# device.net
KiCad netlist of a schematic drawn in EAGLE
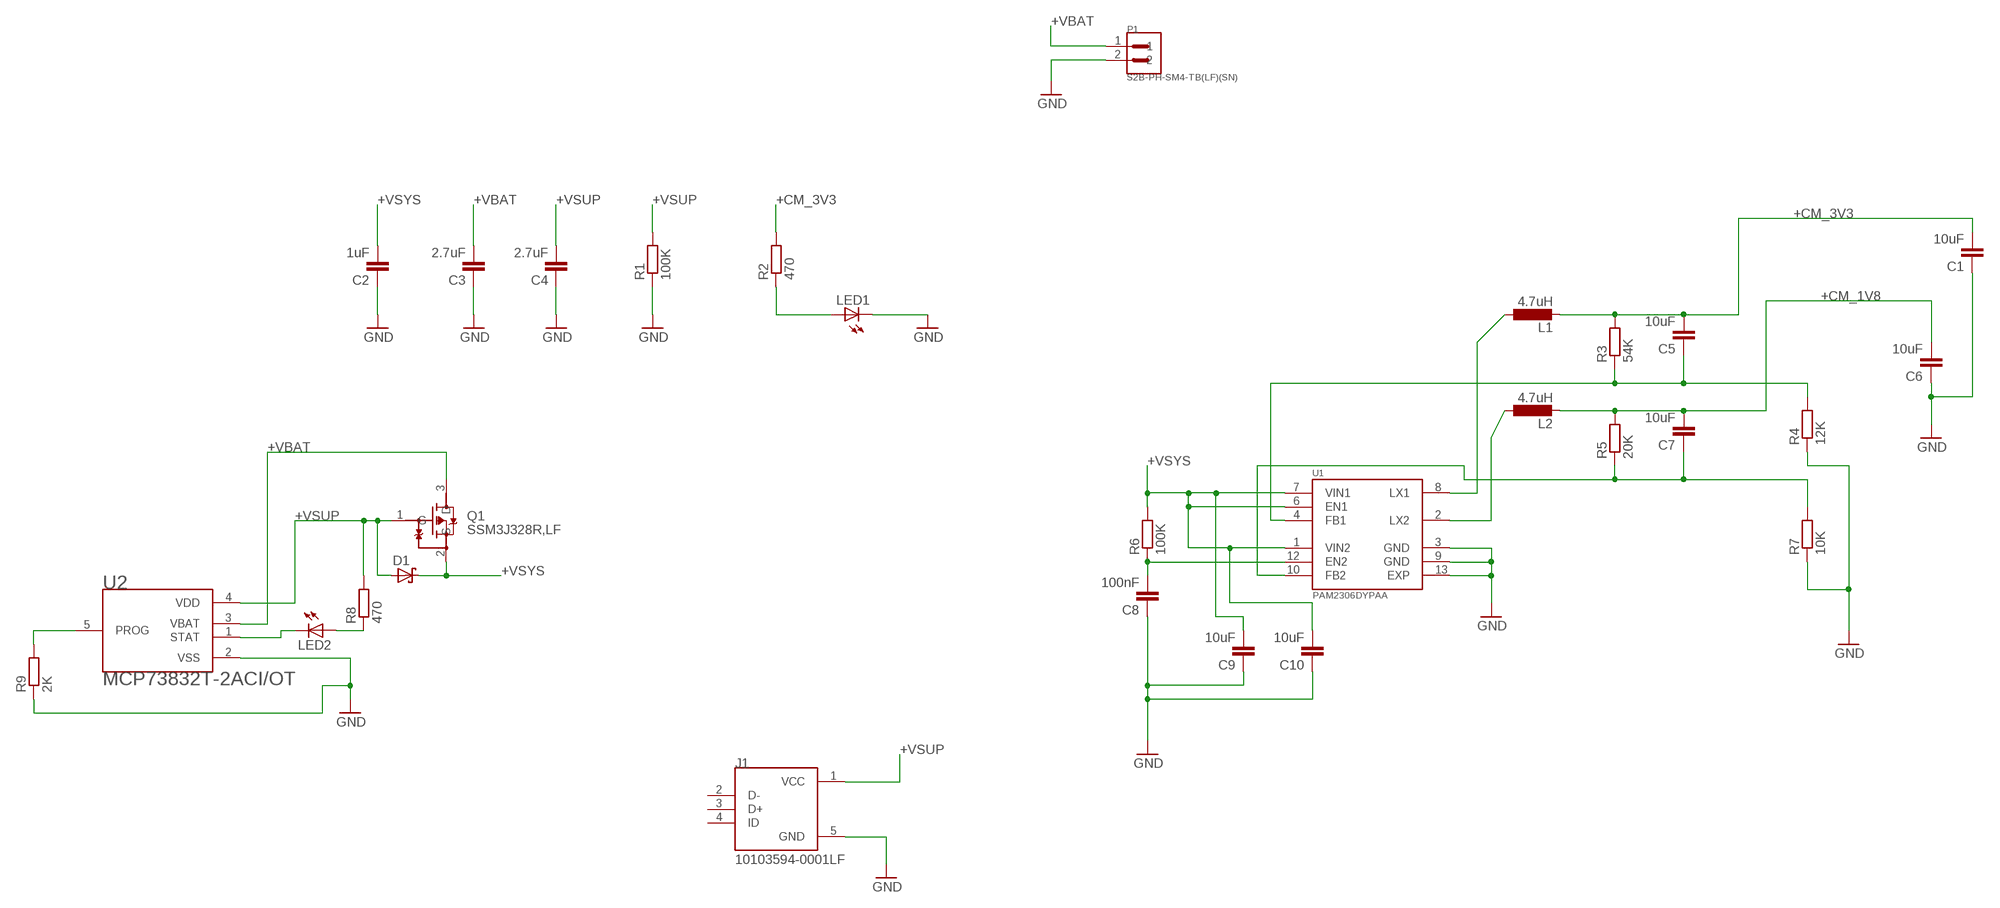
[diagram p0: schematic, sheet 1, part 1 of 2]
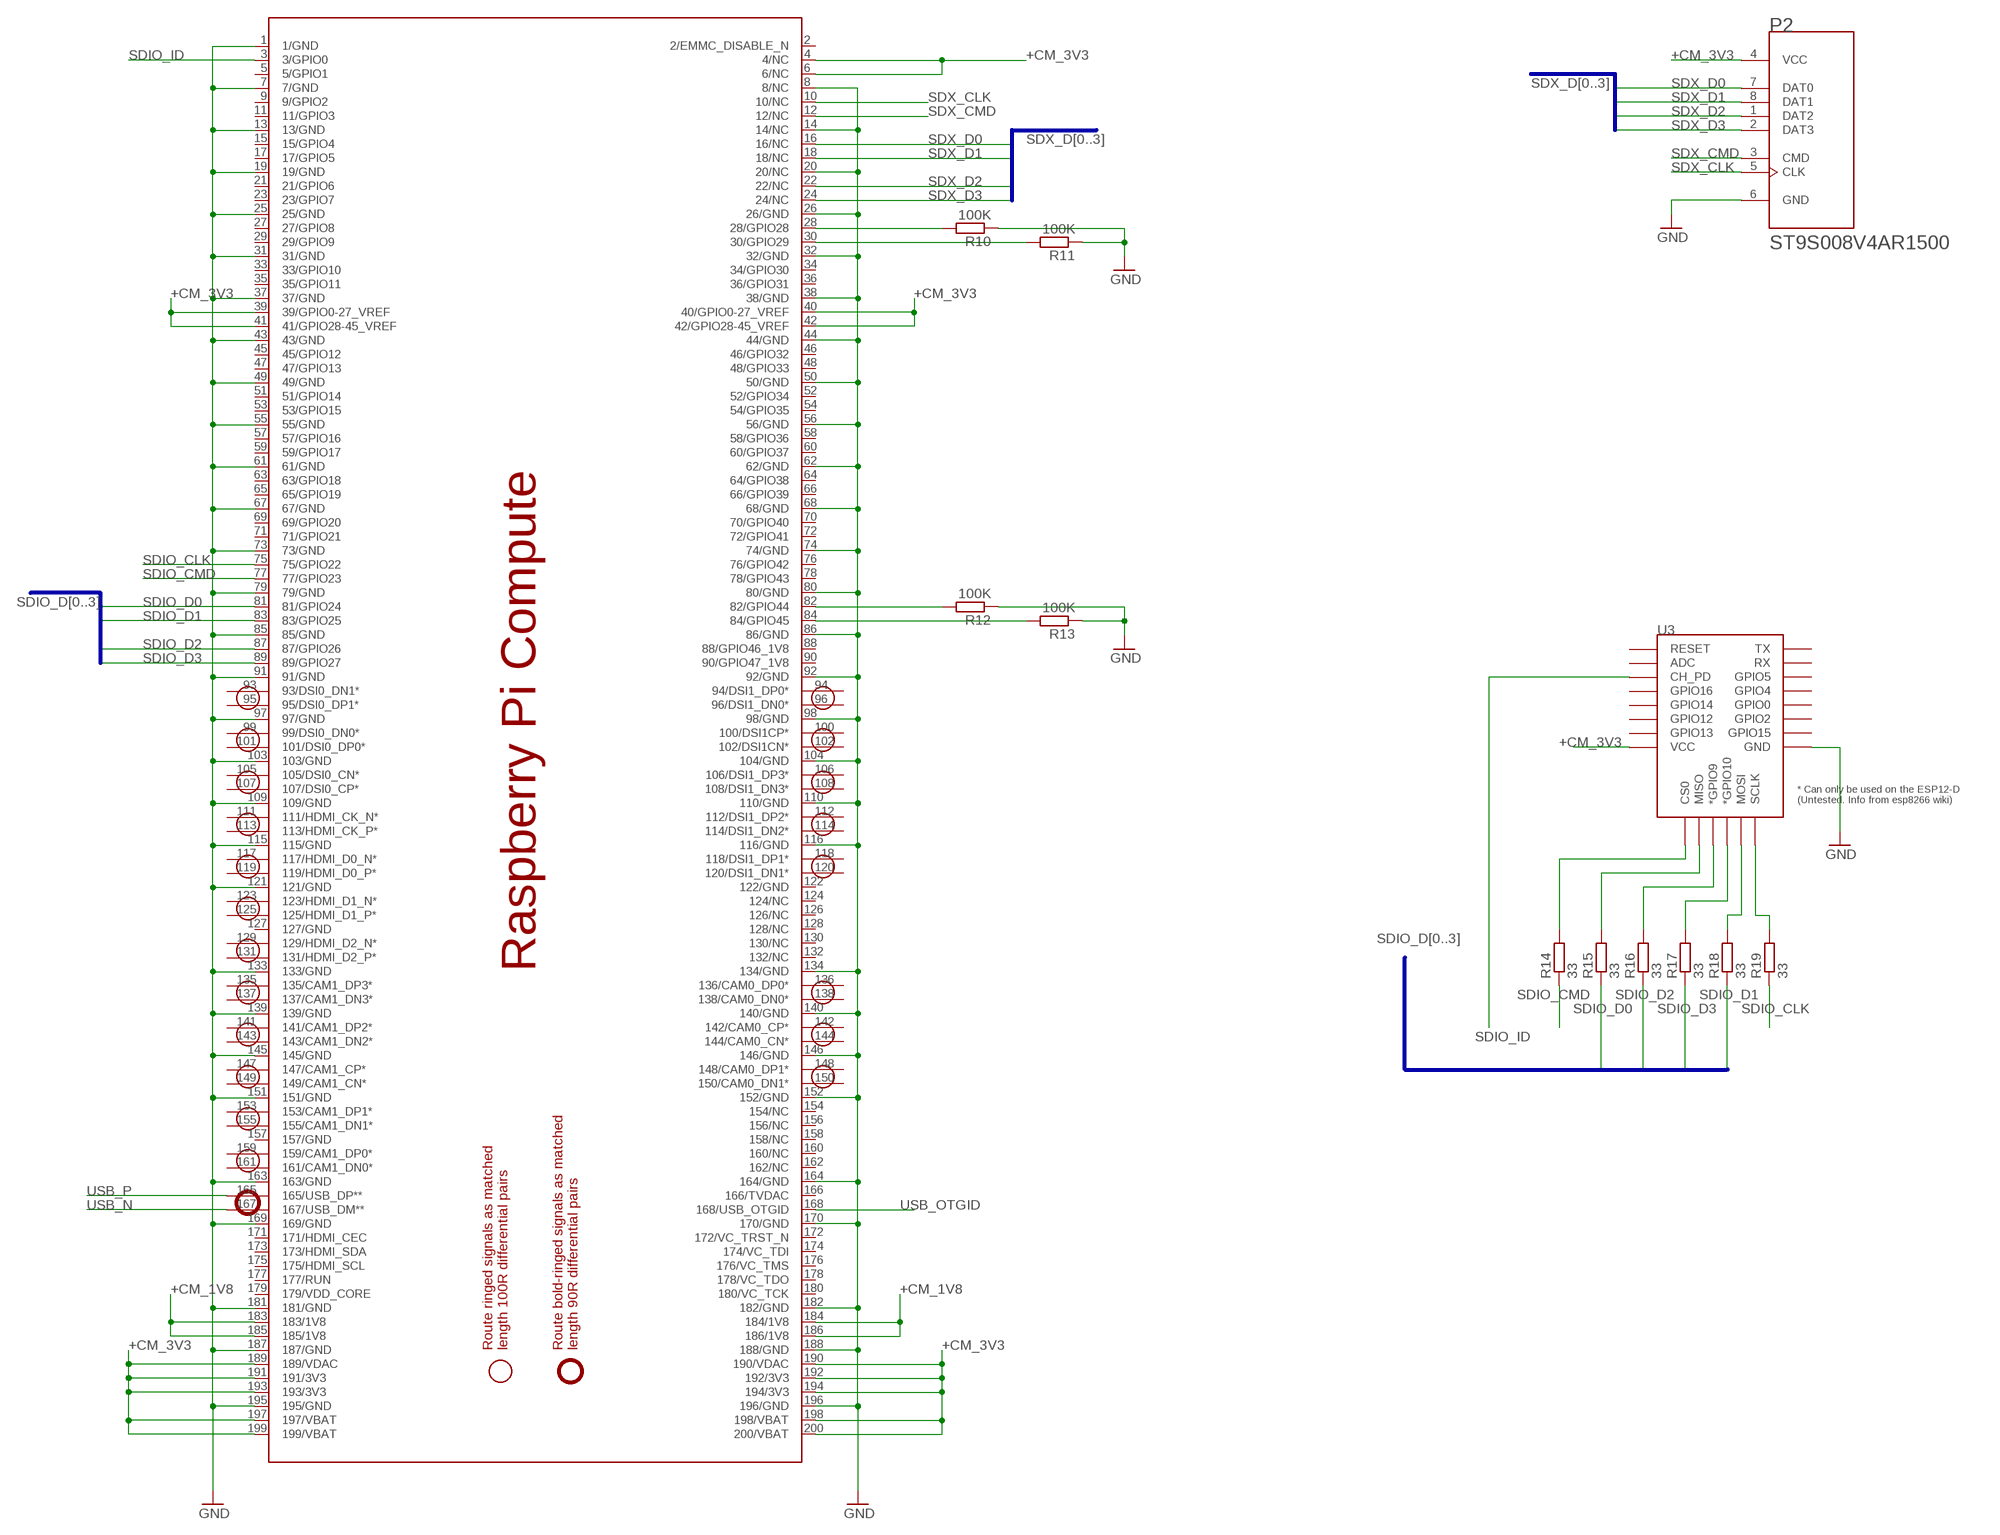
[diagram p1: schematic, sheet 1, part 2 of 2]

(export (version "E")
  (design (tool "Eeschema 10.0.6"))
  (components
    (comp (ref "C1")
      (value "10uF")
      (footprint "eagle-import:C0603")
      (libsource (lib "eagle-import") (part "C-EUC0603"))
    )
    (comp (ref "C2")
      (value "1uF")
      (footprint "eagle-import:C0603")
      (libsource (lib "eagle-import") (part "C-EUC0603"))
    )
    (comp (ref "C3")
      (value "2.7uF")
      (footprint "eagle-import:C0603")
      (libsource (lib "eagle-import") (part "C-EUC0603"))
    )
    (comp (ref "C4")
      (value "2.7uF")
      (footprint "eagle-import:C0603")
      (libsource (lib "eagle-import") (part "C-EUC0603"))
    )
    (comp (ref "C5")
      (value "10uF")
      (footprint "eagle-import:C0603")
      (libsource (lib "eagle-import") (part "C-EUC0603"))
    )
    (comp (ref "C6")
      (value "10uF")
      (footprint "eagle-import:C0603")
      (libsource (lib "eagle-import") (part "C-EUC0603"))
    )
    (comp (ref "C7")
      (value "10uF")
      (footprint "eagle-import:C0603")
      (libsource (lib "eagle-import") (part "C-EUC0603"))
    )
    (comp (ref "C8")
      (value "100nF")
      (footprint "eagle-import:C0603")
      (libsource (lib "eagle-import") (part "C-EUC0603"))
    )
    (comp (ref "C9")
      (value "10uF")
      (footprint "eagle-import:C0603")
      (libsource (lib "eagle-import") (part "C-EUC0603"))
    )
    (comp (ref "C10")
      (value "10uF")
      (footprint "eagle-import:C0603")
      (libsource (lib "eagle-import") (part "C-EUC0603"))
    )
    (comp (ref "D1")
      (value "SCHOTTKY-DIODESMD")
      (footprint "eagle-import:SMB")
      (libsource (lib "eagle-import") (part "SCHOTTKY-DIODESMD"))
    )
    (comp (ref "J1")
      (value "10103594-0001LF")
      (footprint "eagle-import:FCI_10103594-0001LF")
      (fields (field (name "MANUFACTURER") "Framatome"))
      (libsource (lib "eagle-import") (part "10103594-0001LF"))
    )
    (comp (ref "L1")
      (value "4.7uH")
      (footprint "eagle-import:L1812")
      (libsource (lib "eagle-import") (part "L-EUL1812"))
    )
    (comp (ref "L2")
      (value "4.7uH")
      (footprint "eagle-import:L1812")
      (libsource (lib "eagle-import") (part "L-EUL1812"))
    )
    (comp (ref "LED1")
      (value "LEDCHIP-LED0603")
      (footprint "eagle-import:CHIP-LED0603")
      (libsource (lib "eagle-import") (part "LEDCHIP-LED0603"))
    )
    (comp (ref "LED2")
      (value "LEDCHIP-LED0603")
      (footprint "eagle-import:CHIP-LED0603")
      (libsource (lib "eagle-import") (part "LEDCHIP-LED0603"))
    )
    (comp (ref "P1")
      (value "S2B-PH-SM4-TB(LF)(SN)")
      (footprint "eagle-import:JST_S2B-PH-SM4-TB(LF)(SN)")
      (fields (field (name "MANUFACTURER") "JST"))
      (libsource (lib "eagle-import") (part "S2B-PH-SM4-TB(LF)(SN)"))
    )
    (comp (ref "P2")
      (value "ST9S008V4AR1500")
      (footprint "eagle-import:JAE_ST9S008V4AR1500")
      (fields (field (name "MANUFACTURER") "JAE"))
      (libsource (lib "eagle-import") (part "ST9S008V4AR1500"))
    )
    (comp (ref "PCB1")
      (value "RPI_COMPUTE")
      (footprint "eagle-import:RPI_COMPUTE")
      (libsource (lib "eagle-import") (part "RPI_COMPUTE"))
    )
    (comp (ref "Q1")
      (value "SSM3J328R,LF")
      (footprint "eagle-import:SOT95P240X88-3N")
      (fields (field (name "MANUFACTURER") "Toshiba"))
      (libsource (lib "eagle-import") (part "SSM3J328R,LF"))
    )
    (comp (ref "R1")
      (value "100K")
      (footprint "eagle-import:R0603")
      (libsource (lib "eagle-import") (part "R-EU_R0603"))
    )
    (comp (ref "R2")
      (value "470")
      (footprint "eagle-import:R0603")
      (libsource (lib "eagle-import") (part "R-EU_R0603"))
    )
    (comp (ref "R3")
      (value "54K")
      (footprint "eagle-import:R0603")
      (libsource (lib "eagle-import") (part "R-EU_R0603"))
    )
    (comp (ref "R4")
      (value "12K")
      (footprint "eagle-import:R0603")
      (libsource (lib "eagle-import") (part "R-EU_R0603"))
    )
    (comp (ref "R5")
      (value "20K")
      (footprint "eagle-import:R0603")
      (libsource (lib "eagle-import") (part "R-EU_R0603"))
    )
    (comp (ref "R6")
      (value "100K")
      (footprint "eagle-import:R0603")
      (libsource (lib "eagle-import") (part "R-EU_R0603"))
    )
    (comp (ref "R7")
      (value "10K")
      (footprint "eagle-import:R0603")
      (libsource (lib "eagle-import") (part "R-EU_R0603"))
    )
    (comp (ref "R8")
      (value "470")
      (footprint "eagle-import:R0603")
      (libsource (lib "eagle-import") (part "R-EU_R0603"))
    )
    (comp (ref "R9")
      (value "2K")
      (footprint "eagle-import:R0603")
      (libsource (lib "eagle-import") (part "R-EU_R0603"))
    )
    (comp (ref "R10")
      (value "100K")
      (footprint "eagle-import:R0603")
      (libsource (lib "eagle-import") (part "R-EU_R0603"))
    )
    (comp (ref "R11")
      (value "100K")
      (footprint "eagle-import:R0603")
      (libsource (lib "eagle-import") (part "R-EU_R0603"))
    )
    (comp (ref "R12")
      (value "100K")
      (footprint "eagle-import:R0603")
      (libsource (lib "eagle-import") (part "R-EU_R0603"))
    )
    (comp (ref "R13")
      (value "100K")
      (footprint "eagle-import:R0603")
      (libsource (lib "eagle-import") (part "R-EU_R0603"))
    )
    (comp (ref "R14")
      (value "33")
      (footprint "eagle-import:R0603")
      (libsource (lib "eagle-import") (part "R-EU_R0603"))
    )
    (comp (ref "R15")
      (value "33")
      (footprint "eagle-import:R0603")
      (libsource (lib "eagle-import") (part "R-EU_R0603"))
    )
    (comp (ref "R16")
      (value "33")
      (footprint "eagle-import:R0603")
      (libsource (lib "eagle-import") (part "R-EU_R0603"))
    )
    (comp (ref "R17")
      (value "33")
      (footprint "eagle-import:R0603")
      (libsource (lib "eagle-import") (part "R-EU_R0603"))
    )
    (comp (ref "R18")
      (value "33")
      (footprint "eagle-import:R0603")
      (libsource (lib "eagle-import") (part "R-EU_R0603"))
    )
    (comp (ref "R19")
      (value "33")
      (footprint "eagle-import:R0603")
      (libsource (lib "eagle-import") (part "R-EU_R0603"))
    )
    (comp (ref "U1")
      (value "PAM2306DYPAA")
      (footprint "eagle-import:SON45P300X300X80-13N")
      (fields (field (name "MF") "Diodes Inc."))
      (libsource (lib "eagle-import") (part "PAM2306DYPAA"))
    )
    (comp (ref "U2")
      (value "MCP73832T-2ACI/OT")
      (footprint "eagle-import:SOT95P270X145-5N")
      (fields (field (name "MANUFACTURER") "Microchip"))
      (libsource (lib "eagle-import") (part "MCP73832T-2ACI/OT"))
    )
    (comp (ref "U3")
      (value "ESP12ESMD")
      (footprint "eagle-import:ESP12E-SMD")
      (libsource (lib "eagle-import") (part "ESP12ESMD"))
    )
  )
  (nets
    (net (code "1") (name "/+CM_1V8") (class "Default")
      (node (ref "C6") (pin "2") (pinfunction "2_2") (pintype "passive"))
      (node (ref "C7") (pin "2") (pinfunction "2_2") (pintype "passive"))
      (node (ref "L2") (pin "2") (pinfunction "2_2") (pintype "passive"))
      (node (ref "PCB1") (pin "183") (pinfunction "183/1V8_183") (pintype "bidirectional"))
      (node (ref "PCB1") (pin "184") (pinfunction "184/1V8_184") (pintype "bidirectional"))
      (node (ref "PCB1") (pin "185") (pinfunction "185/1V8_185") (pintype "bidirectional"))
      (node (ref "PCB1") (pin "186") (pinfunction "186/1V8_186") (pintype "bidirectional"))
      (node (ref "R5") (pin "2") (pinfunction "2_2") (pintype "passive"))
    )
    (net (code "2") (name "/+CM_3V3") (class "Default")
      (node (ref "C1") (pin "2") (pinfunction "2_2") (pintype "passive"))
      (node (ref "C5") (pin "2") (pinfunction "2_2") (pintype "passive"))
      (node (ref "L1") (pin "2") (pinfunction "2_2") (pintype "passive"))
      (node (ref "P2") (pin "4") (pinfunction "VCC_4") (pintype "power_in"))
      (node (ref "PCB1") (pin "189") (pinfunction "189/VDAC_189") (pintype "bidirectional"))
      (node (ref "PCB1") (pin "190") (pinfunction "190/VDAC_190") (pintype "bidirectional"))
      (node (ref "PCB1") (pin "191") (pinfunction "191/3V3_191") (pintype "bidirectional"))
      (node (ref "PCB1") (pin "192") (pinfunction "192/3V3_192") (pintype "bidirectional"))
      (node (ref "PCB1") (pin "193") (pinfunction "193/3V3_193") (pintype "bidirectional"))
      (node (ref "PCB1") (pin "194") (pinfunction "194/3V3_194") (pintype "bidirectional"))
      (node (ref "PCB1") (pin "197") (pinfunction "197/VBAT_197") (pintype "bidirectional"))
      (node (ref "PCB1") (pin "198") (pinfunction "198/VBAT_198") (pintype "bidirectional"))
      (node (ref "PCB1") (pin "199") (pinfunction "199/VBAT_199") (pintype "bidirectional"))
      (node (ref "PCB1") (pin "200") (pinfunction "200/VBAT_200") (pintype "bidirectional"))
      (node (ref "PCB1") (pin "39") (pinfunction "39/GPIO0-27_VREF_39") (pintype "bidirectional"))
      (node (ref "PCB1") (pin "4") (pinfunction "4/NC_4") (pintype "bidirectional"))
      (node (ref "PCB1") (pin "40") (pinfunction "40/GPIO0-27_VREF_40") (pintype "bidirectional"))
      (node (ref "PCB1") (pin "41") (pinfunction "41/GPIO28-45_VREF_41") (pintype "bidirectional"))
      (node (ref "PCB1") (pin "42") (pinfunction "42/GPIO28-45_VREF_42") (pintype "bidirectional"))
      (node (ref "PCB1") (pin "6") (pinfunction "6/NC_6") (pintype "bidirectional"))
      (node (ref "R2") (pin "2") (pinfunction "2_2") (pintype "passive"))
      (node (ref "R3") (pin "2") (pinfunction "2_2") (pintype "passive"))
      (node (ref "U3") (pin "VCC") (pinfunction "VCC_VCC") (pintype "bidirectional"))
    )
    (net (code "3") (name "/+VBAT") (class "Default")
      (node (ref "C3") (pin "2") (pinfunction "2_2") (pintype "passive"))
      (node (ref "P1") (pin "1") (pinfunction "1_1") (pintype "passive"))
      (node (ref "Q1") (pin "3") (pinfunction "D_3") (pintype "passive"))
      (node (ref "U2") (pin "3") (pinfunction "VBAT_3") (pintype "output"))
    )
    (net (code "4") (name "/+VSUP") (class "Default")
      (node (ref "C4") (pin "2") (pinfunction "2_2") (pintype "passive"))
      (node (ref "D1") (pin "A") (pinfunction "A_A") (pintype "passive"))
      (node (ref "J1") (pin "1") (pinfunction "VCC_1") (pintype "power_in"))
      (node (ref "Q1") (pin "1") (pinfunction "G_1") (pintype "passive"))
      (node (ref "R1") (pin "2") (pinfunction "2_2") (pintype "passive"))
      (node (ref "R8") (pin "2") (pinfunction "2_2") (pintype "passive"))
      (node (ref "U2") (pin "4") (pinfunction "VDD_4") (pintype "power_in"))
    )
    (net (code "5") (name "/+VSYS") (class "Default")
      (node (ref "C10") (pin "2") (pinfunction "2_2") (pintype "passive"))
      (node (ref "C2") (pin "2") (pinfunction "2_2") (pintype "passive"))
      (node (ref "C9") (pin "2") (pinfunction "2_2") (pintype "passive"))
      (node (ref "D1") (pin "C") (pinfunction "C_C") (pintype "passive"))
      (node (ref "Q1") (pin "2") (pinfunction "S_2") (pintype "passive"))
      (node (ref "R6") (pin "2") (pinfunction "2_2") (pintype "passive"))
      (node (ref "U1") (pin "1") (pinfunction "VIN2_1") (pintype "input"))
      (node (ref "U1") (pin "6") (pinfunction "EN1_6") (pintype "input"))
      (node (ref "U1") (pin "7") (pinfunction "VIN1_7") (pintype "input"))
    )
    (net (code "6") (name "/SDIO_CLK") (class "Default")
      (node (ref "PCB1") (pin "75") (pinfunction "75/GPIO22_75") (pintype "bidirectional"))
      (node (ref "R19") (pin "1") (pinfunction "1_1") (pintype "passive"))
    )
    (net (code "7") (name "/SDIO_CMD") (class "Default")
      (node (ref "PCB1") (pin "77") (pinfunction "77/GPIO23_77") (pintype "bidirectional"))
      (node (ref "R14") (pin "1") (pinfunction "1_1") (pintype "passive"))
    )
    (net (code "8") (name "/SDIO_D0") (class "Default")
      (node (ref "PCB1") (pin "81") (pinfunction "81/GPIO24_81") (pintype "bidirectional"))
      (node (ref "R15") (pin "1") (pinfunction "1_1") (pintype "passive"))
    )
    (net (code "9") (name "/SDIO_D1") (class "Default")
      (node (ref "PCB1") (pin "83") (pinfunction "83/GPIO25_83") (pintype "bidirectional"))
      (node (ref "R18") (pin "1") (pinfunction "1_1") (pintype "passive"))
    )
    (net (code "10") (name "/SDIO_D2") (class "Default")
      (node (ref "PCB1") (pin "87") (pinfunction "87/GPIO26_87") (pintype "bidirectional"))
      (node (ref "R16") (pin "1") (pinfunction "1_1") (pintype "passive"))
    )
    (net (code "11") (name "/SDIO_D3") (class "Default")
      (node (ref "PCB1") (pin "89") (pinfunction "89/GPIO27_89") (pintype "bidirectional"))
      (node (ref "R17") (pin "1") (pinfunction "1_1") (pintype "passive"))
    )
    (net (code "13") (name "/SDIO_ID") (class "Default")
      (node (ref "PCB1") (pin "3") (pinfunction "3/GPIO0_3") (pintype "bidirectional"))
      (node (ref "U3") (pin "CH_PD") (pinfunction "CH_PD_CH_PD") (pintype "bidirectional"))
    )
    (net (code "14") (name "/SDX_CLK") (class "Default")
      (node (ref "P2") (pin "5") (pinfunction "CLK_5") (pintype "input"))
      (node (ref "PCB1") (pin "10") (pinfunction "10/NC_10") (pintype "bidirectional"))
    )
    (net (code "15") (name "/SDX_CMD") (class "Default")
      (node (ref "P2") (pin "3") (pinfunction "CMD_3") (pintype "input"))
      (node (ref "PCB1") (pin "12") (pinfunction "12/NC_12") (pintype "bidirectional"))
    )
    (net (code "16") (name "/SDX_D0") (class "Default")
      (node (ref "P2") (pin "7") (pinfunction "DAT0_7") (pintype "bidirectional"))
      (node (ref "PCB1") (pin "16") (pinfunction "16/NC_16") (pintype "bidirectional"))
    )
    (net (code "17") (name "/SDX_D1") (class "Default")
      (node (ref "P2") (pin "8") (pinfunction "DAT1_8") (pintype "bidirectional"))
      (node (ref "PCB1") (pin "18") (pinfunction "18/NC_18") (pintype "bidirectional"))
    )
    (net (code "18") (name "/SDX_D2") (class "Default")
      (node (ref "P2") (pin "1") (pinfunction "DAT2_1") (pintype "bidirectional"))
      (node (ref "PCB1") (pin "22") (pinfunction "22/NC_22") (pintype "bidirectional"))
    )
    (net (code "19") (name "/SDX_D3") (class "Default")
      (node (ref "P2") (pin "2") (pinfunction "DAT3_2") (pintype "bidirectional"))
      (node (ref "PCB1") (pin "24") (pinfunction "24/NC_24") (pintype "bidirectional"))
    )
    (net (code "21") (name "/USB_N") (class "Default")
      (node (ref "PCB1") (pin "167") (pinfunction "167/USB_DM**_167") (pintype "bidirectional"))
    )
    (net (code "22") (name "/USB_OTGID") (class "Default")
      (node (ref "PCB1") (pin "168") (pinfunction "168/USB_OTGID_168") (pintype "bidirectional"))
    )
    (net (code "23") (name "/USB_P") (class "Default")
      (node (ref "PCB1") (pin "165") (pinfunction "165/USB_DP**_165") (pintype "bidirectional"))
    )
    (net (code "24") (name "GND") (class "Default")
      (node (ref "C1") (pin "1") (pinfunction "1_1") (pintype "passive"))
      (node (ref "C10") (pin "1") (pinfunction "1_1") (pintype "passive"))
      (node (ref "C2") (pin "1") (pinfunction "1_1") (pintype "passive"))
      (node (ref "C3") (pin "1") (pinfunction "1_1") (pintype "passive"))
      (node (ref "C4") (pin "1") (pinfunction "1_1") (pintype "passive"))
      (node (ref "C6") (pin "1") (pinfunction "1_1") (pintype "passive"))
      (node (ref "C8") (pin "1") (pinfunction "1_1") (pintype "passive"))
      (node (ref "C9") (pin "1") (pinfunction "1_1") (pintype "passive"))
      (node (ref "J1") (pin "5") (pinfunction "GND_5") (pintype "power_in"))
      (node (ref "LED1") (pin "C") (pinfunction "C_C") (pintype "passive"))
      (node (ref "P1") (pin "2") (pinfunction "2_2") (pintype "passive"))
      (node (ref "P2") (pin "6") (pinfunction "GND_6") (pintype "power_in"))
      (node (ref "PCB1") (pin "1") (pinfunction "1/GND_1") (pintype "bidirectional"))
      (node (ref "PCB1") (pin "103") (pinfunction "103/GND_103") (pintype "bidirectional"))
      (node (ref "PCB1") (pin "104") (pinfunction "104/GND_104") (pintype "bidirectional"))
      (node (ref "PCB1") (pin "109") (pinfunction "109/GND_109") (pintype "bidirectional"))
      (node (ref "PCB1") (pin "110") (pinfunction "110/GND_110") (pintype "bidirectional"))
      (node (ref "PCB1") (pin "115") (pinfunction "115/GND_115") (pintype "bidirectional"))
      (node (ref "PCB1") (pin "116") (pinfunction "116/GND_116") (pintype "bidirectional"))
      (node (ref "PCB1") (pin "121") (pinfunction "121/GND_121") (pintype "bidirectional"))
      (node (ref "PCB1") (pin "13") (pinfunction "13/GND_13") (pintype "bidirectional"))
      (node (ref "PCB1") (pin "133") (pinfunction "133/GND_133") (pintype "bidirectional"))
      (node (ref "PCB1") (pin "134") (pinfunction "134/GND_134") (pintype "bidirectional"))
      (node (ref "PCB1") (pin "139") (pinfunction "139/GND_139") (pintype "bidirectional"))
      (node (ref "PCB1") (pin "14") (pinfunction "14/NC_14") (pintype "bidirectional"))
      (node (ref "PCB1") (pin "140") (pinfunction "140/GND_140") (pintype "bidirectional"))
      (node (ref "PCB1") (pin "145") (pinfunction "145/GND_145") (pintype "bidirectional"))
      (node (ref "PCB1") (pin "146") (pinfunction "146/GND_146") (pintype "bidirectional"))
      (node (ref "PCB1") (pin "151") (pinfunction "151/GND_151") (pintype "bidirectional"))
      (node (ref "PCB1") (pin "152") (pinfunction "152/GND_152") (pintype "bidirectional"))
      (node (ref "PCB1") (pin "163") (pinfunction "163/GND_163") (pintype "bidirectional"))
      (node (ref "PCB1") (pin "164") (pinfunction "164/GND_164") (pintype "bidirectional"))
      (node (ref "PCB1") (pin "169") (pinfunction "169/GND_169") (pintype "bidirectional"))
      (node (ref "PCB1") (pin "170") (pinfunction "170/GND_170") (pintype "bidirectional"))
      (node (ref "PCB1") (pin "181") (pinfunction "181/GND_181") (pintype "bidirectional"))
      (node (ref "PCB1") (pin "182") (pinfunction "182/GND_182") (pintype "bidirectional"))
      (node (ref "PCB1") (pin "187") (pinfunction "187/GND_187") (pintype "bidirectional"))
      (node (ref "PCB1") (pin "188") (pinfunction "188/GND_188") (pintype "bidirectional"))
      (node (ref "PCB1") (pin "19") (pinfunction "19/GND_19") (pintype "bidirectional"))
      (node (ref "PCB1") (pin "195") (pinfunction "195/GND_195") (pintype "bidirectional"))
      (node (ref "PCB1") (pin "196") (pinfunction "196/GND_196") (pintype "bidirectional"))
      (node (ref "PCB1") (pin "20") (pinfunction "20/NC_20") (pintype "bidirectional"))
      (node (ref "PCB1") (pin "25") (pinfunction "25/GND_25") (pintype "bidirectional"))
      (node (ref "PCB1") (pin "26") (pinfunction "26/GND_26") (pintype "bidirectional"))
      (node (ref "PCB1") (pin "31") (pinfunction "31/GND_31") (pintype "bidirectional"))
      (node (ref "PCB1") (pin "32") (pinfunction "32/GND_32") (pintype "bidirectional"))
      (node (ref "PCB1") (pin "37") (pinfunction "37/GND_37") (pintype "bidirectional"))
      (node (ref "PCB1") (pin "38") (pinfunction "38/GND_38") (pintype "bidirectional"))
      (node (ref "PCB1") (pin "43") (pinfunction "43/GND_43") (pintype "bidirectional"))
      (node (ref "PCB1") (pin "44") (pinfunction "44/GND_44") (pintype "bidirectional"))
      (node (ref "PCB1") (pin "49") (pinfunction "49/GND_49") (pintype "bidirectional"))
      (node (ref "PCB1") (pin "50") (pinfunction "50/GND_50") (pintype "bidirectional"))
      (node (ref "PCB1") (pin "55") (pinfunction "55/GND_55") (pintype "bidirectional"))
      (node (ref "PCB1") (pin "56") (pinfunction "56/GND_56") (pintype "bidirectional"))
      (node (ref "PCB1") (pin "61") (pinfunction "61/GND_61") (pintype "bidirectional"))
      (node (ref "PCB1") (pin "62") (pinfunction "62/GND_62") (pintype "bidirectional"))
      (node (ref "PCB1") (pin "67") (pinfunction "67/GND_67") (pintype "bidirectional"))
      (node (ref "PCB1") (pin "68") (pinfunction "68/GND_68") (pintype "bidirectional"))
      (node (ref "PCB1") (pin "7") (pinfunction "7/GND_7") (pintype "bidirectional"))
      (node (ref "PCB1") (pin "73") (pinfunction "73/GND_73") (pintype "bidirectional"))
      (node (ref "PCB1") (pin "74") (pinfunction "74/GND_74") (pintype "bidirectional"))
      (node (ref "PCB1") (pin "79") (pinfunction "79/GND_79") (pintype "bidirectional"))
      (node (ref "PCB1") (pin "8") (pinfunction "8/NC_8") (pintype "bidirectional"))
      (node (ref "PCB1") (pin "80") (pinfunction "80/GND_80") (pintype "bidirectional"))
      (node (ref "PCB1") (pin "85") (pinfunction "85/GND_85") (pintype "bidirectional"))
      (node (ref "PCB1") (pin "86") (pinfunction "86/GND_86") (pintype "bidirectional"))
      (node (ref "PCB1") (pin "91") (pinfunction "91/GND_91") (pintype "bidirectional"))
      (node (ref "PCB1") (pin "92") (pinfunction "92/GND_92") (pintype "bidirectional"))
      (node (ref "PCB1") (pin "97") (pinfunction "97/GND_97") (pintype "bidirectional"))
      (node (ref "PCB1") (pin "98") (pinfunction "98/GND_98") (pintype "bidirectional"))
      (node (ref "R1") (pin "1") (pinfunction "1_1") (pintype "passive"))
      (node (ref "R10") (pin "1") (pinfunction "1_1") (pintype "passive"))
      (node (ref "R11") (pin "1") (pinfunction "1_1") (pintype "passive"))
      (node (ref "R12") (pin "1") (pinfunction "1_1") (pintype "passive"))
      (node (ref "R13") (pin "1") (pinfunction "1_1") (pintype "passive"))
      (node (ref "R4") (pin "1") (pinfunction "1_1") (pintype "passive"))
      (node (ref "R7") (pin "1") (pinfunction "1_1") (pintype "passive"))
      (node (ref "R9") (pin "1") (pinfunction "1_1") (pintype "passive"))
      (node (ref "U1") (pin "13") (pinfunction "EXP_13") (pintype "power_in"))
      (node (ref "U1") (pin "3") (pinfunction "GND_3") (pintype "power_in"))
      (node (ref "U1") (pin "9") (pinfunction "GND_9") (pintype "power_in"))
      (node (ref "U2") (pin "2") (pinfunction "VSS_2") (pintype "power_in"))
      (node (ref "U3") (pin "GND") (pinfunction "GND_GND") (pintype "bidirectional"))
    )
    (net (code "25") (name "Net-(LED1-PadA)") (class "Default")
      (node (ref "LED1") (pin "A") (pinfunction "A_A") (pintype "passive"))
      (node (ref "R2") (pin "1") (pinfunction "1_1") (pintype "passive"))
    )
    (net (code "26") (name "Net-(LED2-PadA)") (class "Default")
      (node (ref "LED2") (pin "A") (pinfunction "A_A") (pintype "passive"))
      (node (ref "R8") (pin "1") (pinfunction "1_1") (pintype "passive"))
    )
    (net (code "27") (name "Net-(PCB1-28{slash}GPIO28)") (class "Default")
      (node (ref "PCB1") (pin "28") (pinfunction "28/GPIO28_28") (pintype "bidirectional"))
      (node (ref "R10") (pin "2") (pinfunction "2_2") (pintype "passive"))
    )
    (net (code "28") (name "Net-(PCB1-30{slash}GPIO29)") (class "Default")
      (node (ref "PCB1") (pin "30") (pinfunction "30/GPIO29_30") (pintype "bidirectional"))
      (node (ref "R11") (pin "2") (pinfunction "2_2") (pintype "passive"))
    )
    (net (code "29") (name "Net-(PCB1-82{slash}GPIO44)") (class "Default")
      (node (ref "PCB1") (pin "82") (pinfunction "82/GPIO44_82") (pintype "bidirectional"))
      (node (ref "R12") (pin "2") (pinfunction "2_2") (pintype "passive"))
    )
    (net (code "30") (name "Net-(PCB1-84{slash}GPIO45)") (class "Default")
      (node (ref "PCB1") (pin "84") (pinfunction "84/GPIO45_84") (pintype "bidirectional"))
      (node (ref "R13") (pin "2") (pinfunction "2_2") (pintype "passive"))
    )
    (net (code "31") (name "Net-(R14-Pad2)") (class "Default")
      (node (ref "R14") (pin "2") (pinfunction "2_2") (pintype "passive"))
      (node (ref "U3") (pin "CS0") (pinfunction "CS0_CS0") (pintype "bidirectional"))
    )
    (net (code "32") (name "Net-(R15-Pad2)") (class "Default")
      (node (ref "R15") (pin "2") (pinfunction "2_2") (pintype "passive"))
      (node (ref "U3") (pin "MISO") (pinfunction "MISO_MISO") (pintype "bidirectional"))
    )
    (net (code "33") (name "Net-(R18-Pad2)") (class "Default")
      (node (ref "R18") (pin "2") (pinfunction "2_2") (pintype "passive"))
      (node (ref "U3") (pin "MOSI") (pinfunction "MOSI_MOSI") (pintype "bidirectional"))
    )
    (net (code "34") (name "Net-(R19-Pad2)") (class "Default")
      (node (ref "R19") (pin "2") (pinfunction "2_2") (pintype "passive"))
      (node (ref "U3") (pin "SCLK") (pinfunction "SCLK_SCLK") (pintype "bidirectional"))
    )
    (net (code "35") (name "Net-(U1-EN2)") (class "Default")
      (node (ref "C8") (pin "2") (pinfunction "2_2") (pintype "passive"))
      (node (ref "R6") (pin "1") (pinfunction "1_1") (pintype "passive"))
      (node (ref "U1") (pin "12") (pinfunction "EN2_12") (pintype "input"))
    )
    (net (code "36") (name "Net-(U1-FB1)") (class "Default")
      (node (ref "C5") (pin "1") (pinfunction "1_1") (pintype "passive"))
      (node (ref "R3") (pin "1") (pinfunction "1_1") (pintype "passive"))
      (node (ref "R4") (pin "2") (pinfunction "2_2") (pintype "passive"))
      (node (ref "U1") (pin "4") (pinfunction "FB1_4") (pintype "input"))
    )
    (net (code "37") (name "Net-(U1-FB2)") (class "Default")
      (node (ref "C7") (pin "1") (pinfunction "1_1") (pintype "passive"))
      (node (ref "R5") (pin "1") (pinfunction "1_1") (pintype "passive"))
      (node (ref "R7") (pin "2") (pinfunction "2_2") (pintype "passive"))
      (node (ref "U1") (pin "10") (pinfunction "FB2_10") (pintype "input"))
    )
    (net (code "38") (name "Net-(U1-LX1)") (class "Default")
      (node (ref "L1") (pin "1") (pinfunction "1_1") (pintype "passive"))
      (node (ref "U1") (pin "8") (pinfunction "LX1_8") (pintype "output"))
    )
    (net (code "39") (name "Net-(U1-LX2)") (class "Default")
      (node (ref "L2") (pin "1") (pinfunction "1_1") (pintype "passive"))
      (node (ref "U1") (pin "2") (pinfunction "LX2_2") (pintype "output"))
    )
    (net (code "40") (name "Net-(U2-PROG)") (class "Default")
      (node (ref "R9") (pin "2") (pinfunction "2_2") (pintype "passive"))
      (node (ref "U2") (pin "5") (pinfunction "PROG_5") (pintype "input"))
    )
    (net (code "41") (name "Net-(U2-STAT)") (class "Default")
      (node (ref "LED2") (pin "C") (pinfunction "C_C") (pintype "passive"))
      (node (ref "U2") (pin "1") (pinfunction "STAT_1") (pintype "output"))
    )
    (net (code "42") (name "Net-(U3-*GPIO9)") (class "Default")
      (node (ref "R16") (pin "2") (pinfunction "2_2") (pintype "passive"))
      (node (ref "U3") (pin "GPIO9") (pinfunction "*GPIO9_GPIO9") (pintype "bidirectional"))
    )
    (net (code "43") (name "Net-(U3-*GPIO10)") (class "Default")
      (node (ref "R17") (pin "2") (pinfunction "2_2") (pintype "passive"))
      (node (ref "U3") (pin "GPIO10") (pinfunction "*GPIO10_GPIO10") (pintype "bidirectional"))
    )
    (net (code "44") (name "unconnected-(J1-D+-Pad3)") (class "Default")
      (node (ref "J1") (pin "3") (pinfunction "D+_3") (pintype "bidirectional"))
    )
    (net (code "45") (name "unconnected-(J1-D--Pad2)") (class "Default")
      (node (ref "J1") (pin "2") (pinfunction "D-_2") (pintype "bidirectional"))
    )
    (net (code "46") (name "unconnected-(J1-ID-Pad4)") (class "Default")
      (node (ref "J1") (pin "4") (pinfunction "ID_4") (pintype "bidirectional"))
    )
    (net (code "47") (name "unconnected-(PCB1-2{slash}EMMC_DISABLE_N-Pad2)") (class "Default")
      (node (ref "PCB1") (pin "2") (pinfunction "2/EMMC_DISABLE_N_2") (pintype "bidirectional"))
    )
    (net (code "48") (name "unconnected-(PCB1-5{slash}GPIO1-Pad5)") (class "Default")
      (node (ref "PCB1") (pin "5") (pinfunction "5/GPIO1_5") (pintype "bidirectional"))
    )
    (net (code "49") (name "unconnected-(PCB1-9{slash}GPIO2-Pad9)") (class "Default")
      (node (ref "PCB1") (pin "9") (pinfunction "9/GPIO2_9") (pintype "bidirectional"))
    )
    (net (code "50") (name "unconnected-(PCB1-11{slash}GPIO3-Pad11)") (class "Default")
      (node (ref "PCB1") (pin "11") (pinfunction "11/GPIO3_11") (pintype "bidirectional"))
    )
    (net (code "51") (name "unconnected-(PCB1-15{slash}GPIO4-Pad15)") (class "Default")
      (node (ref "PCB1") (pin "15") (pinfunction "15/GPIO4_15") (pintype "bidirectional"))
    )
    (net (code "52") (name "unconnected-(PCB1-17{slash}GPIO5-Pad17)") (class "Default")
      (node (ref "PCB1") (pin "17") (pinfunction "17/GPIO5_17") (pintype "bidirectional"))
    )
    (net (code "53") (name "unconnected-(PCB1-21{slash}GPIO6-Pad21)") (class "Default")
      (node (ref "PCB1") (pin "21") (pinfunction "21/GPIO6_21") (pintype "bidirectional"))
    )
    (net (code "54") (name "unconnected-(PCB1-23{slash}GPIO7-Pad23)") (class "Default")
      (node (ref "PCB1") (pin "23") (pinfunction "23/GPIO7_23") (pintype "bidirectional"))
    )
    (net (code "55") (name "unconnected-(PCB1-27{slash}GPIO8-Pad27)") (class "Default")
      (node (ref "PCB1") (pin "27") (pinfunction "27/GPIO8_27") (pintype "bidirectional"))
    )
    (net (code "56") (name "unconnected-(PCB1-29{slash}GPIO9-Pad29)") (class "Default")
      (node (ref "PCB1") (pin "29") (pinfunction "29/GPIO9_29") (pintype "bidirectional"))
    )
    (net (code "57") (name "unconnected-(PCB1-33{slash}GPIO10-Pad33)") (class "Default")
      (node (ref "PCB1") (pin "33") (pinfunction "33/GPIO10_33") (pintype "bidirectional"))
    )
    (net (code "58") (name "unconnected-(PCB1-34{slash}GPIO30-Pad34)") (class "Default")
      (node (ref "PCB1") (pin "34") (pinfunction "34/GPIO30_34") (pintype "bidirectional"))
    )
    (net (code "59") (name "unconnected-(PCB1-35{slash}GPIO11-Pad35)") (class "Default")
      (node (ref "PCB1") (pin "35") (pinfunction "35/GPIO11_35") (pintype "bidirectional"))
    )
    (net (code "60") (name "unconnected-(PCB1-36{slash}GPIO31-Pad36)") (class "Default")
      (node (ref "PCB1") (pin "36") (pinfunction "36/GPIO31_36") (pintype "bidirectional"))
    )
    (net (code "61") (name "unconnected-(PCB1-45{slash}GPIO12-Pad45)") (class "Default")
      (node (ref "PCB1") (pin "45") (pinfunction "45/GPIO12_45") (pintype "bidirectional"))
    )
    (net (code "62") (name "unconnected-(PCB1-46{slash}GPIO32-Pad46)") (class "Default")
      (node (ref "PCB1") (pin "46") (pinfunction "46/GPIO32_46") (pintype "bidirectional"))
    )
    (net (code "63") (name "unconnected-(PCB1-47{slash}GPIO13-Pad47)") (class "Default")
      (node (ref "PCB1") (pin "47") (pinfunction "47/GPIO13_47") (pintype "bidirectional"))
    )
    (net (code "64") (name "unconnected-(PCB1-48{slash}GPIO33-Pad48)") (class "Default")
      (node (ref "PCB1") (pin "48") (pinfunction "48/GPIO33_48") (pintype "bidirectional"))
    )
    (net (code "65") (name "unconnected-(PCB1-51{slash}GPIO14-Pad51)") (class "Default")
      (node (ref "PCB1") (pin "51") (pinfunction "51/GPIO14_51") (pintype "bidirectional"))
    )
    (net (code "66") (name "unconnected-(PCB1-52{slash}GPIO34-Pad52)") (class "Default")
      (node (ref "PCB1") (pin "52") (pinfunction "52/GPIO34_52") (pintype "bidirectional"))
    )
    (net (code "67") (name "unconnected-(PCB1-53{slash}GPIO15-Pad53)") (class "Default")
      (node (ref "PCB1") (pin "53") (pinfunction "53/GPIO15_53") (pintype "bidirectional"))
    )
    (net (code "68") (name "unconnected-(PCB1-54{slash}GPIO35-Pad54)") (class "Default")
      (node (ref "PCB1") (pin "54") (pinfunction "54/GPIO35_54") (pintype "bidirectional"))
    )
    (net (code "69") (name "unconnected-(PCB1-57{slash}GPIO16-Pad57)") (class "Default")
      (node (ref "PCB1") (pin "57") (pinfunction "57/GPIO16_57") (pintype "bidirectional"))
    )
    (net (code "70") (name "unconnected-(PCB1-58{slash}GPIO36-Pad58)") (class "Default")
      (node (ref "PCB1") (pin "58") (pinfunction "58/GPIO36_58") (pintype "bidirectional"))
    )
    (net (code "71") (name "unconnected-(PCB1-59{slash}GPIO17-Pad59)") (class "Default")
      (node (ref "PCB1") (pin "59") (pinfunction "59/GPIO17_59") (pintype "bidirectional"))
    )
    (net (code "72") (name "unconnected-(PCB1-60{slash}GPIO37-Pad60)") (class "Default")
      (node (ref "PCB1") (pin "60") (pinfunction "60/GPIO37_60") (pintype "bidirectional"))
    )
    (net (code "73") (name "unconnected-(PCB1-63{slash}GPIO18-Pad63)") (class "Default")
      (node (ref "PCB1") (pin "63") (pinfunction "63/GPIO18_63") (pintype "bidirectional"))
    )
    (net (code "74") (name "unconnected-(PCB1-64{slash}GPIO38-Pad64)") (class "Default")
      (node (ref "PCB1") (pin "64") (pinfunction "64/GPIO38_64") (pintype "bidirectional"))
    )
    (net (code "75") (name "unconnected-(PCB1-65{slash}GPIO19-Pad65)") (class "Default")
      (node (ref "PCB1") (pin "65") (pinfunction "65/GPIO19_65") (pintype "bidirectional"))
    )
    (net (code "76") (name "unconnected-(PCB1-66{slash}GPIO39-Pad66)") (class "Default")
      (node (ref "PCB1") (pin "66") (pinfunction "66/GPIO39_66") (pintype "bidirectional"))
    )
    (net (code "77") (name "unconnected-(PCB1-69{slash}GPIO20-Pad69)") (class "Default")
      (node (ref "PCB1") (pin "69") (pinfunction "69/GPIO20_69") (pintype "bidirectional"))
    )
    (net (code "78") (name "unconnected-(PCB1-70{slash}GPIO40-Pad70)") (class "Default")
      (node (ref "PCB1") (pin "70") (pinfunction "70/GPIO40_70") (pintype "bidirectional"))
    )
    (net (code "79") (name "unconnected-(PCB1-71{slash}GPIO21-Pad71)") (class "Default")
      (node (ref "PCB1") (pin "71") (pinfunction "71/GPIO21_71") (pintype "bidirectional"))
    )
    (net (code "80") (name "unconnected-(PCB1-72{slash}GPIO41-Pad72)") (class "Default")
      (node (ref "PCB1") (pin "72") (pinfunction "72/GPIO41_72") (pintype "bidirectional"))
    )
    (net (code "81") (name "unconnected-(PCB1-76{slash}GPIO42-Pad76)") (class "Default")
      (node (ref "PCB1") (pin "76") (pinfunction "76/GPIO42_76") (pintype "bidirectional"))
    )
    (net (code "82") (name "unconnected-(PCB1-78{slash}GPIO43-Pad78)") (class "Default")
      (node (ref "PCB1") (pin "78") (pinfunction "78/GPIO43_78") (pintype "bidirectional"))
    )
    (net (code "83") (name "unconnected-(PCB1-88{slash}GPIO46_1V8-Pad88)") (class "Default")
      (node (ref "PCB1") (pin "88") (pinfunction "88/GPIO46_1V8_88") (pintype "bidirectional"))
    )
    (net (code "84") (name "unconnected-(PCB1-90{slash}GPIO47_1V8-Pad90)") (class "Default")
      (node (ref "PCB1") (pin "90") (pinfunction "90/GPIO47_1V8_90") (pintype "bidirectional"))
    )
    (net (code "85") (name "unconnected-(PCB1-93{slash}DSI0_DN1*-Pad93)") (class "Default")
      (node (ref "PCB1") (pin "93") (pinfunction "93/DSI0_DN1*_93") (pintype "bidirectional"))
    )
    (net (code "86") (name "unconnected-(PCB1-94{slash}DSI1_DP0*-Pad94)") (class "Default")
      (node (ref "PCB1") (pin "94") (pinfunction "94/DSI1_DP0*_94") (pintype "bidirectional"))
    )
    (net (code "87") (name "unconnected-(PCB1-95{slash}DSI0_DP1*-Pad95)") (class "Default")
      (node (ref "PCB1") (pin "95") (pinfunction "95/DSI0_DP1*_95") (pintype "bidirectional"))
    )
    (net (code "88") (name "unconnected-(PCB1-96{slash}DSI1_DN0*-Pad96)") (class "Default")
      (node (ref "PCB1") (pin "96") (pinfunction "96/DSI1_DN0*_96") (pintype "bidirectional"))
    )
    (net (code "89") (name "unconnected-(PCB1-99{slash}DSI0_DN0*-Pad99)") (class "Default")
      (node (ref "PCB1") (pin "99") (pinfunction "99/DSI0_DN0*_99") (pintype "bidirectional"))
    )
    (net (code "90") (name "unconnected-(PCB1-100{slash}DSI1CP*-Pad100)") (class "Default")
      (node (ref "PCB1") (pin "100") (pinfunction "100/DSI1CP*_100") (pintype "bidirectional"))
    )
    (net (code "91") (name "unconnected-(PCB1-101{slash}DSI0_DP0*-Pad101)") (class "Default")
      (node (ref "PCB1") (pin "101") (pinfunction "101/DSI0_DP0*_101") (pintype "bidirectional"))
    )
    (net (code "92") (name "unconnected-(PCB1-102{slash}DSI1CN*-Pad102)") (class "Default")
      (node (ref "PCB1") (pin "102") (pinfunction "102/DSI1CN*_102") (pintype "bidirectional"))
    )
    (net (code "93") (name "unconnected-(PCB1-105{slash}DSI0_CN*-Pad105)") (class "Default")
      (node (ref "PCB1") (pin "105") (pinfunction "105/DSI0_CN*_105") (pintype "bidirectional"))
    )
    (net (code "94") (name "unconnected-(PCB1-106{slash}DSI1_DP3*-Pad106)") (class "Default")
      (node (ref "PCB1") (pin "106") (pinfunction "106/DSI1_DP3*_106") (pintype "bidirectional"))
    )
    (net (code "95") (name "unconnected-(PCB1-107{slash}DSI0_CP*-Pad107)") (class "Default")
      (node (ref "PCB1") (pin "107") (pinfunction "107/DSI0_CP*_107") (pintype "bidirectional"))
    )
    (net (code "96") (name "unconnected-(PCB1-108{slash}DSI1_DN3*-Pad108)") (class "Default")
      (node (ref "PCB1") (pin "108") (pinfunction "108/DSI1_DN3*_108") (pintype "bidirectional"))
    )
    (net (code "97") (name "unconnected-(PCB1-111{slash}HDMI_CK_N*-Pad111)") (class "Default")
      (node (ref "PCB1") (pin "111") (pinfunction "111/HDMI_CK_N*_111") (pintype "bidirectional"))
    )
    (net (code "98") (name "unconnected-(PCB1-112{slash}DSI1_DP2*-Pad112)") (class "Default")
      (node (ref "PCB1") (pin "112") (pinfunction "112/DSI1_DP2*_112") (pintype "bidirectional"))
    )
    (net (code "99") (name "unconnected-(PCB1-113{slash}HDMI_CK_P*-Pad113)") (class "Default")
      (node (ref "PCB1") (pin "113") (pinfunction "113/HDMI_CK_P*_113") (pintype "bidirectional"))
    )
    (net (code "100") (name "unconnected-(PCB1-114{slash}DSI1_DN2*-Pad114)") (class "Default")
      (node (ref "PCB1") (pin "114") (pinfunction "114/DSI1_DN2*_114") (pintype "bidirectional"))
    )
    (net (code "101") (name "unconnected-(PCB1-117{slash}HDMI_D0_N*-Pad117)") (class "Default")
      (node (ref "PCB1") (pin "117") (pinfunction "117/HDMI_D0_N*_117") (pintype "bidirectional"))
    )
    (net (code "102") (name "unconnected-(PCB1-118{slash}DSI1_DP1*-Pad118)") (class "Default")
      (node (ref "PCB1") (pin "118") (pinfunction "118/DSI1_DP1*_118") (pintype "bidirectional"))
    )
    (net (code "103") (name "unconnected-(PCB1-119{slash}HDMI_D0_P*-Pad119)") (class "Default")
      (node (ref "PCB1") (pin "119") (pinfunction "119/HDMI_D0_P*_119") (pintype "bidirectional"))
    )
    (net (code "104") (name "unconnected-(PCB1-120{slash}DSI1_DN1*-Pad120)") (class "Default")
      (node (ref "PCB1") (pin "120") (pinfunction "120/DSI1_DN1*_120") (pintype "bidirectional"))
    )
    (net (code "105") (name "unconnected-(PCB1-122{slash}GND-Pad122)") (class "Default")
      (node (ref "PCB1") (pin "122") (pinfunction "122/GND_122") (pintype "bidirectional"))
    )
    (net (code "106") (name "unconnected-(PCB1-123{slash}HDMI_D1_N*-Pad123)") (class "Default")
      (node (ref "PCB1") (pin "123") (pinfunction "123/HDMI_D1_N*_123") (pintype "bidirectional"))
    )
    (net (code "107") (name "unconnected-(PCB1-124{slash}NC-Pad124)") (class "Default")
      (node (ref "PCB1") (pin "124") (pinfunction "124/NC_124") (pintype "bidirectional"))
    )
    (net (code "108") (name "unconnected-(PCB1-125{slash}HDMI_D1_P*-Pad125)") (class "Default")
      (node (ref "PCB1") (pin "125") (pinfunction "125/HDMI_D1_P*_125") (pintype "bidirectional"))
    )
    (net (code "109") (name "unconnected-(PCB1-126{slash}NC-Pad126)") (class "Default")
      (node (ref "PCB1") (pin "126") (pinfunction "126/NC_126") (pintype "bidirectional"))
    )
    (net (code "110") (name "unconnected-(PCB1-127{slash}GND-Pad127)") (class "Default")
      (node (ref "PCB1") (pin "127") (pinfunction "127/GND_127") (pintype "bidirectional"))
    )
    (net (code "111") (name "unconnected-(PCB1-128{slash}NC-Pad128)") (class "Default")
      (node (ref "PCB1") (pin "128") (pinfunction "128/NC_128") (pintype "bidirectional"))
    )
    (net (code "112") (name "unconnected-(PCB1-129{slash}HDMI_D2_N*-Pad129)") (class "Default")
      (node (ref "PCB1") (pin "129") (pinfunction "129/HDMI_D2_N*_129") (pintype "bidirectional"))
    )
    (net (code "113") (name "unconnected-(PCB1-130{slash}NC-Pad130)") (class "Default")
      (node (ref "PCB1") (pin "130") (pinfunction "130/NC_130") (pintype "bidirectional"))
    )
    (net (code "114") (name "unconnected-(PCB1-131{slash}HDMI_D2_P*-Pad131)") (class "Default")
      (node (ref "PCB1") (pin "131") (pinfunction "131/HDMI_D2_P*_131") (pintype "bidirectional"))
    )
    (net (code "115") (name "unconnected-(PCB1-132{slash}NC-Pad132)") (class "Default")
      (node (ref "PCB1") (pin "132") (pinfunction "132/NC_132") (pintype "bidirectional"))
    )
    (net (code "116") (name "unconnected-(PCB1-135{slash}CAM1_DP3*-Pad135)") (class "Default")
      (node (ref "PCB1") (pin "135") (pinfunction "135/CAM1_DP3*_135") (pintype "bidirectional"))
    )
    (net (code "117") (name "unconnected-(PCB1-136{slash}CAM0_DP0*-Pad136)") (class "Default")
      (node (ref "PCB1") (pin "136") (pinfunction "136/CAM0_DP0*_136") (pintype "bidirectional"))
    )
    (net (code "118") (name "unconnected-(PCB1-137{slash}CAM1_DN3*-Pad137)") (class "Default")
      (node (ref "PCB1") (pin "137") (pinfunction "137/CAM1_DN3*_137") (pintype "bidirectional"))
    )
    (net (code "119") (name "unconnected-(PCB1-138{slash}CAM0_DN0*-Pad138)") (class "Default")
      (node (ref "PCB1") (pin "138") (pinfunction "138/CAM0_DN0*_138") (pintype "bidirectional"))
    )
    (net (code "120") (name "unconnected-(PCB1-141{slash}CAM1_DP2*-Pad141)") (class "Default")
      (node (ref "PCB1") (pin "141") (pinfunction "141/CAM1_DP2*_141") (pintype "bidirectional"))
    )
    (net (code "121") (name "unconnected-(PCB1-142{slash}CAM0_CP*-Pad142)") (class "Default")
      (node (ref "PCB1") (pin "142") (pinfunction "142/CAM0_CP*_142") (pintype "bidirectional"))
    )
    (net (code "122") (name "unconnected-(PCB1-143{slash}CAM1_DN2*-Pad143)") (class "Default")
      (node (ref "PCB1") (pin "143") (pinfunction "143/CAM1_DN2*_143") (pintype "bidirectional"))
    )
    (net (code "123") (name "unconnected-(PCB1-144{slash}CAM0_CN*-Pad144)") (class "Default")
      (node (ref "PCB1") (pin "144") (pinfunction "144/CAM0_CN*_144") (pintype "bidirectional"))
    )
    (net (code "124") (name "unconnected-(PCB1-147{slash}CAM1_CP*-Pad147)") (class "Default")
      (node (ref "PCB1") (pin "147") (pinfunction "147/CAM1_CP*_147") (pintype "bidirectional"))
    )
    (net (code "125") (name "unconnected-(PCB1-148{slash}CAM0_DP1*-Pad148)") (class "Default")
      (node (ref "PCB1") (pin "148") (pinfunction "148/CAM0_DP1*_148") (pintype "bidirectional"))
    )
    (net (code "126") (name "unconnected-(PCB1-149{slash}CAM1_CN*-Pad149)") (class "Default")
      (node (ref "PCB1") (pin "149") (pinfunction "149/CAM1_CN*_149") (pintype "bidirectional"))
    )
    (net (code "127") (name "unconnected-(PCB1-150{slash}CAM0_DN1*-Pad150)") (class "Default")
      (node (ref "PCB1") (pin "150") (pinfunction "150/CAM0_DN1*_150") (pintype "bidirectional"))
    )
    (net (code "128") (name "unconnected-(PCB1-153{slash}CAM1_DP1*-Pad153)") (class "Default")
      (node (ref "PCB1") (pin "153") (pinfunction "153/CAM1_DP1*_153") (pintype "bidirectional"))
    )
    (net (code "129") (name "unconnected-(PCB1-154{slash}NC-Pad154)") (class "Default")
      (node (ref "PCB1") (pin "154") (pinfunction "154/NC_154") (pintype "bidirectional"))
    )
    (net (code "130") (name "unconnected-(PCB1-155{slash}CAM1_DN1*-Pad155)") (class "Default")
      (node (ref "PCB1") (pin "155") (pinfunction "155/CAM1_DN1*_155") (pintype "bidirectional"))
    )
    (net (code "131") (name "unconnected-(PCB1-156{slash}NC-Pad156)") (class "Default")
      (node (ref "PCB1") (pin "156") (pinfunction "156/NC_156") (pintype "bidirectional"))
    )
    (net (code "132") (name "unconnected-(PCB1-157{slash}GND-Pad157)") (class "Default")
      (node (ref "PCB1") (pin "157") (pinfunction "157/GND_157") (pintype "bidirectional"))
    )
    (net (code "133") (name "unconnected-(PCB1-158{slash}NC-Pad158)") (class "Default")
      (node (ref "PCB1") (pin "158") (pinfunction "158/NC_158") (pintype "bidirectional"))
    )
    (net (code "134") (name "unconnected-(PCB1-159{slash}CAM1_DP0*-Pad159)") (class "Default")
      (node (ref "PCB1") (pin "159") (pinfunction "159/CAM1_DP0*_159") (pintype "bidirectional"))
    )
    (net (code "135") (name "unconnected-(PCB1-160{slash}NC-Pad160)") (class "Default")
      (node (ref "PCB1") (pin "160") (pinfunction "160/NC_160") (pintype "bidirectional"))
    )
    (net (code "136") (name "unconnected-(PCB1-161{slash}CAM1_DN0*-Pad161)") (class "Default")
      (node (ref "PCB1") (pin "161") (pinfunction "161/CAM1_DN0*_161") (pintype "bidirectional"))
    )
    (net (code "137") (name "unconnected-(PCB1-162{slash}NC-Pad162)") (class "Default")
      (node (ref "PCB1") (pin "162") (pinfunction "162/NC_162") (pintype "bidirectional"))
    )
    (net (code "138") (name "unconnected-(PCB1-166{slash}TVDAC-Pad166)") (class "Default")
      (node (ref "PCB1") (pin "166") (pinfunction "166/TVDAC_166") (pintype "bidirectional"))
    )
    (net (code "139") (name "unconnected-(PCB1-171{slash}HDMI_CEC-Pad171)") (class "Default")
      (node (ref "PCB1") (pin "171") (pinfunction "171/HDMI_CEC_171") (pintype "bidirectional"))
    )
    (net (code "140") (name "unconnected-(PCB1-172{slash}VC_TRST_N-Pad172)") (class "Default")
      (node (ref "PCB1") (pin "172") (pinfunction "172/VC_TRST_N_172") (pintype "bidirectional"))
    )
    (net (code "141") (name "unconnected-(PCB1-173{slash}HDMI_SDA-Pad173)") (class "Default")
      (node (ref "PCB1") (pin "173") (pinfunction "173/HDMI_SDA_173") (pintype "bidirectional"))
    )
    (net (code "142") (name "unconnected-(PCB1-174{slash}VC_TDI-Pad174)") (class "Default")
      (node (ref "PCB1") (pin "174") (pinfunction "174/VC_TDI_174") (pintype "bidirectional"))
    )
    (net (code "143") (name "unconnected-(PCB1-175{slash}HDMI_SCL-Pad175)") (class "Default")
      (node (ref "PCB1") (pin "175") (pinfunction "175/HDMI_SCL_175") (pintype "bidirectional"))
    )
    (net (code "144") (name "unconnected-(PCB1-176{slash}VC_TMS-Pad176)") (class "Default")
      (node (ref "PCB1") (pin "176") (pinfunction "176/VC_TMS_176") (pintype "bidirectional"))
    )
    (net (code "145") (name "unconnected-(PCB1-177{slash}RUN-Pad177)") (class "Default")
      (node (ref "PCB1") (pin "177") (pinfunction "177/RUN_177") (pintype "bidirectional"))
    )
    (net (code "146") (name "unconnected-(PCB1-178{slash}VC_TDO-Pad178)") (class "Default")
      (node (ref "PCB1") (pin "178") (pinfunction "178/VC_TDO_178") (pintype "bidirectional"))
    )
    (net (code "147") (name "unconnected-(PCB1-179{slash}VDD_CORE-Pad179)") (class "Default")
      (node (ref "PCB1") (pin "179") (pinfunction "179/VDD_CORE_179") (pintype "bidirectional"))
    )
    (net (code "148") (name "unconnected-(PCB1-180{slash}VC_TCK-Pad180)") (class "Default")
      (node (ref "PCB1") (pin "180") (pinfunction "180/VC_TCK_180") (pintype "bidirectional"))
    )
    (net (code "149") (name "unconnected-(U3-PadADC)") (class "Default")
      (node (ref "U3") (pin "ADC") (pinfunction "ADC_ADC") (pintype "bidirectional"))
    )
    (net (code "150") (name "unconnected-(U3-PadGPIO0)") (class "Default")
      (node (ref "U3") (pin "GPIO0") (pinfunction "GPIO0_GPIO0") (pintype "bidirectional"))
    )
    (net (code "151") (name "unconnected-(U3-PadGPIO2)") (class "Default")
      (node (ref "U3") (pin "GPIO2") (pinfunction "GPIO2_GPIO2") (pintype "bidirectional"))
    )
    (net (code "152") (name "unconnected-(U3-PadGPIO4)") (class "Default")
      (node (ref "U3") (pin "GPIO4") (pinfunction "GPIO4_GPIO4") (pintype "bidirectional"))
    )
    (net (code "153") (name "unconnected-(U3-PadGPIO5)") (class "Default")
      (node (ref "U3") (pin "GPIO5") (pinfunction "GPIO5_GPIO5") (pintype "bidirectional"))
    )
    (net (code "154") (name "unconnected-(U3-PadGPIO12)") (class "Default")
      (node (ref "U3") (pin "GPIO12") (pinfunction "GPIO12_GPIO12") (pintype "bidirectional"))
    )
    (net (code "155") (name "unconnected-(U3-PadGPIO13)") (class "Default")
      (node (ref "U3") (pin "GPIO13") (pinfunction "GPIO13_GPIO13") (pintype "bidirectional"))
    )
    (net (code "156") (name "unconnected-(U3-PadGPIO14)") (class "Default")
      (node (ref "U3") (pin "GPIO14") (pinfunction "GPIO14_GPIO14") (pintype "bidirectional"))
    )
    (net (code "157") (name "unconnected-(U3-PadGPIO15)") (class "Default")
      (node (ref "U3") (pin "GPIO15") (pinfunction "GPIO15_GPIO15") (pintype "bidirectional"))
    )
    (net (code "158") (name "unconnected-(U3-PadGPIO16)") (class "Default")
      (node (ref "U3") (pin "GPIO16") (pinfunction "GPIO16_GPIO16") (pintype "bidirectional"))
    )
    (net (code "159") (name "unconnected-(U3-PadRESET)") (class "Default")
      (node (ref "U3") (pin "RESET") (pinfunction "RESET_RESET") (pintype "bidirectional"))
    )
    (net (code "160") (name "unconnected-(U3-RX-PadRXD0)") (class "Default")
      (node (ref "U3") (pin "RXD0") (pinfunction "RX_RXD0") (pintype "bidirectional"))
    )
    (net (code "161") (name "unconnected-(U3-TX-PadTXD0)") (class "Default")
      (node (ref "U3") (pin "TXD0") (pinfunction "TX_TXD0") (pintype "bidirectional"))
    )
  )
)
